# 03_SigPart.net
KiCad netlist of a schematic drawn in EasyEDA Pro
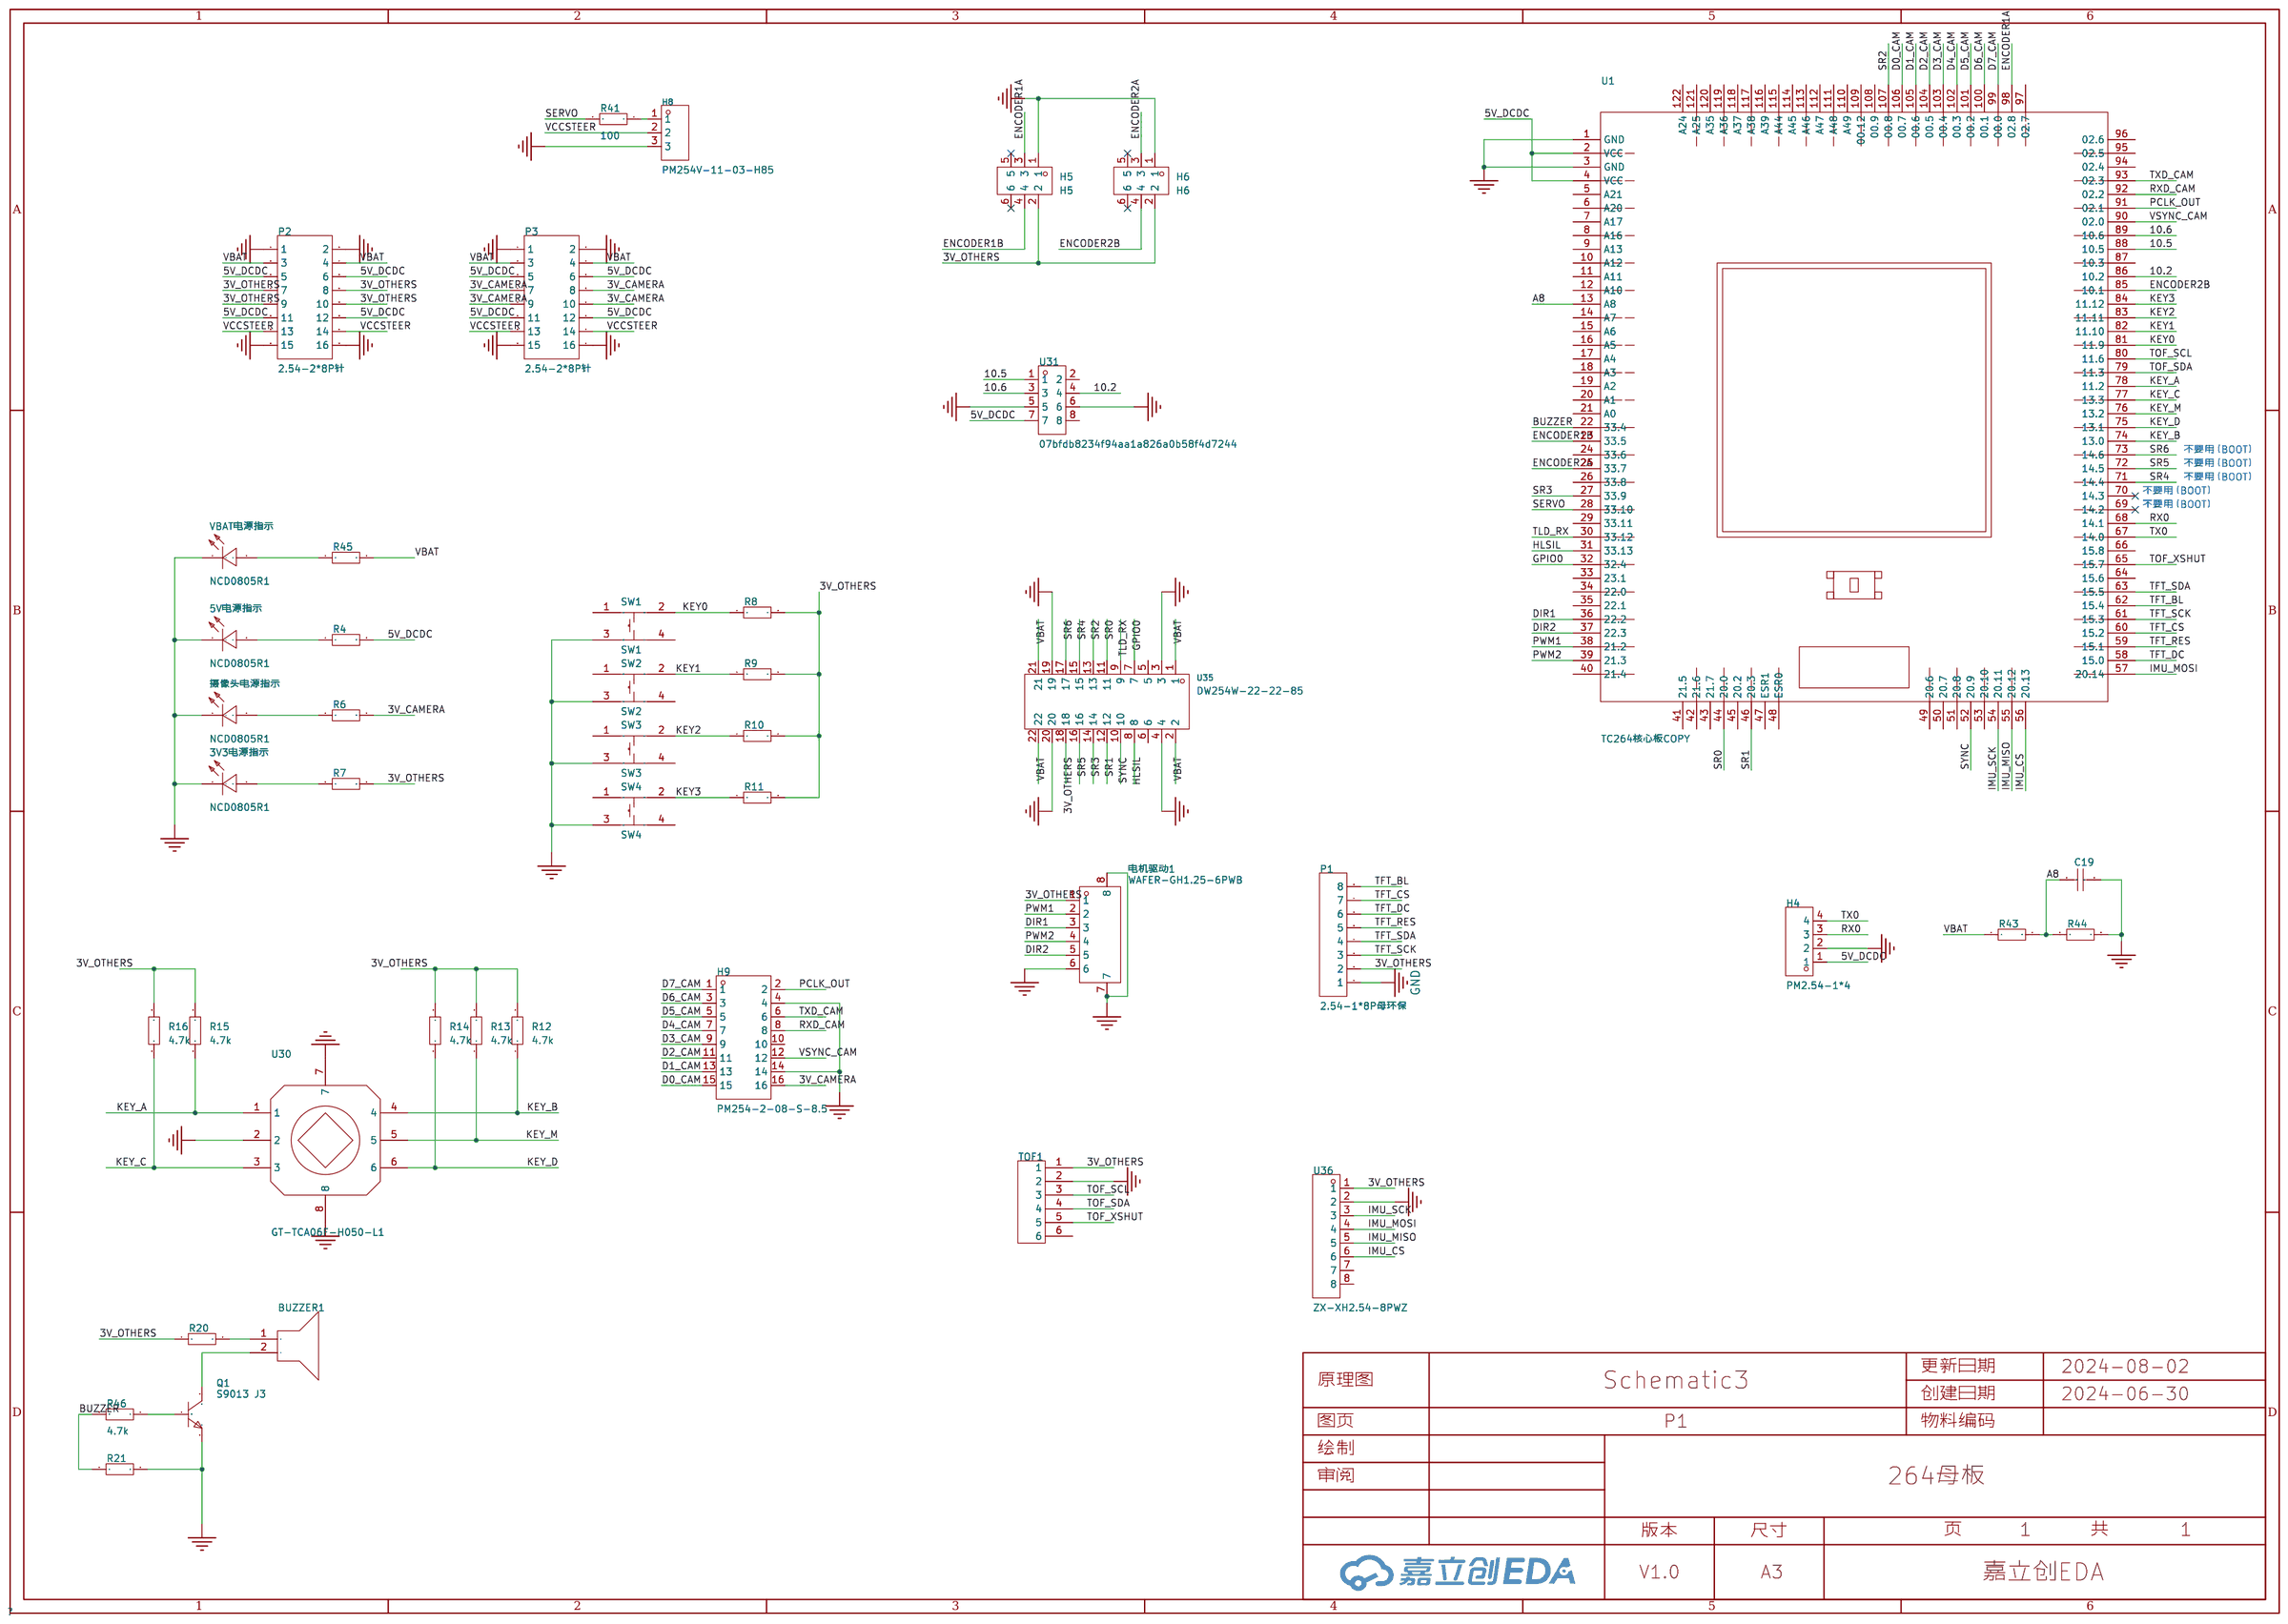
[diagram p0: schematic sheet]

(export (version "E")
  (design (tool "Eeschema 10.0.6"))
  (components
    (comp (ref "3V3电源指示")
      (value "NCD0805R1")
      (footprint "easyedapro:LED0805-RD")
      (description "发光颜色:红灯;")
      (fields (field (name "Manufacturer") "国星光电"))
      (libsource (lib "easyedapro") (part "FC-2012HRK-620D"))
    )
    (comp (ref "5V电源指示")
      (value "NCD0805R1")
      (footprint "easyedapro:LED0805-RD")
      (description "发光颜色:红灯;")
      (fields (field (name "Manufacturer") "国星光电"))
      (libsource (lib "easyedapro") (part "FC-2012HRK-620D"))
    )
    (comp (ref "BUZZER1")
      (value "SFN-1270-0540-35P5.0")
      (footprint "easyedapro:BUZ-TH_BD12.5-P5.00-D0.9")
      (description "驱动方式：无源(外部驱动) 构造类型：压电式 额定电压：5V 频率：4000Hz 声压(SPL)：80dB@5V,10cm 直径(φD)：12.6mm 高度：7.5mm")
      (fields (field (name "Manufacturer") "SS(海旭)"))
      (libsource (lib "easyedapro") (part "BUZZER"))
    )
    (comp (ref "C19")
      (value "100nF")
      (footprint "easyedapro:C0805")
      (libsource (lib "easyedapro") (part "电容-0805C"))
    )
    (comp (ref "H4")
      (value "PM2.54-1*4")
      (footprint "easyedapro:HDR-TH_4P-P2.54-V-F")
      (fields (field (name "Manufacturer") "ZHOURI(洲日)"))
      (libsource (lib "easyedapro") (part "PM2.54-1*4"))
    )
    (comp (ref "H5")
      (value "H5")
      (footprint "easyedapro:HDR-SMD_6P-P2.54-V-M-R2-C5-S7.4")
      (fields
        (field (name "Manufacturer Part") "X6521WVS-2x03H-C60D74")
        (field (name "Manufacturer") "XKB Connectivity(中国星坤)")
      )
      (libsource (lib "easyedapro") (part "X6521WVS-2x03H-C60D74"))
    )
    (comp (ref "H6")
      (value "H6")
      (footprint "easyedapro:HDR-SMD_6P-P2.54-V-M-R2-C5-S7.4")
      (fields
        (field (name "Manufacturer Part") "X6521WVS-2x03H-C60D74")
        (field (name "Manufacturer") "XKB Connectivity(中国星坤)")
      )
      (libsource (lib "easyedapro") (part "X6521WVS-2x03H-C60D74"))
    )
    (comp (ref "H8")
      (value "PM254V-11-03-H85")
      (footprint "easyedapro:HDR-TH_3P-P2.54-V-F")
      (description "排数:单排;总孔位数:3P;间距:2.54mm;插孔结构:1x3P;")
      (fields (field (name "Manufacturer") "XFCN(兴飞)"))
      (libsource (lib "easyedapro") (part "PM254_1*3"))
    )
    (comp (ref "H9")
      (value "PM254-2-08-S-8.5")
      (footprint "easyedapro:HDR-SMD_16P-P2.54-V-F-R2-C8-LS7.1")
      (fields (field (name "Manufacturer") "HCTL(华灿天禄)"))
      (libsource (lib "easyedapro") (part "PM254-2-08-S-8.5"))
    )
    (comp (ref "P1")
      (value "2.54-1*8P母环保")
      (footprint "easyedapro:HDR-TH_8P-P2.54-V-F-1")
      (description "排数:单排;总孔位数:8;间距:2.54mm;插孔结构:1x8P;行距:-;安装类型:直插;塑高:-;触头材质:-;触头镀层:-;")
      (fields (field (name "Manufacturer") "BOOMELE(博穆精密)"))
      (libsource (lib "easyedapro") (part "Header-Female-2.54_1x8"))
    )
    (comp (ref "P2")
      (value "2.54-2*8P针")
      (footprint "easyedapro:HDR-TH_16P-P2.54-V-M-R2-C8-S2.54")
      (fields (field (name "Manufacturer") "BOOMELE(博穆精密)"))
      (libsource (lib "easyedapro") (part "Header-Male-2.54_2x8"))
    )
    (comp (ref "P3")
      (value "2.54-2*8P针")
      (footprint "easyedapro:HDR-TH_16P-P2.54-V-M-R2-C8-S2.54")
      (fields (field (name "Manufacturer") "BOOMELE(博穆精密)"))
      (libsource (lib "easyedapro") (part "Header-Male-2.54_2x8"))
    )
    (comp (ref "Q1")
      (value "S9013 J3")
      (footprint "easyedapro:SOT-23-3_L2.9-W1.3-P1.90-LS2.4-BR")
      (description "晶体管类型:NPN;集电极电流(Ic):500mA;集射极击穿电压(Vceo):25V;功率(Pd):300mW;直流电流增益(hFE@Ic,Vce):200@50mA,1V;")
      (fields (field (name "Manufacturer") "CJ(江苏长电/长晶)"))
      (libsource (lib "easyedapro") (part "S9013 J3"))
    )
    (comp (ref "R4")
      (value "4.7k")
      (footprint "easyedapro:R0805")
      (description "电阻类型:厚膜电阻;阻值:1kΩ;精度:±1%;功率:125mW;温度系数:±100ppm/°C;最大工作电压:150V;工作温度范围:-55°C~+155°C;")
      (libsource (lib "easyedapro") (part "电阻_0805"))
    )
    (comp (ref "R6")
      (value "4.7k")
      (footprint "easyedapro:R0805")
      (description "电阻类型:厚膜电阻;阻值:1kΩ;精度:±1%;功率:125mW;温度系数:±100ppm/°C;最大工作电压:150V;工作温度范围:-55°C~+155°C;")
      (libsource (lib "easyedapro") (part "电阻_0805"))
    )
    (comp (ref "R7")
      (value "4.7k")
      (footprint "easyedapro:R0805")
      (description "电阻类型:厚膜电阻;阻值:1kΩ;精度:±1%;功率:125mW;温度系数:±100ppm/°C;最大工作电压:150V;工作温度范围:-55°C~+155°C;")
      (libsource (lib "easyedapro") (part "电阻_0805"))
    )
    (comp (ref "R8")
      (value "4.7k")
      (footprint "easyedapro:R0805")
      (description "电阻类型:厚膜电阻;阻值:1kΩ;精度:±1%;功率:125mW;温度系数:±100ppm/°C;最大工作电压:150V;工作温度范围:-55°C~+155°C;")
      (libsource (lib "easyedapro") (part "电阻_0805"))
    )
    (comp (ref "R9")
      (value "4.7k")
      (footprint "easyedapro:R0805")
      (description "电阻类型:厚膜电阻;阻值:1kΩ;精度:±1%;功率:125mW;温度系数:±100ppm/°C;最大工作电压:150V;工作温度范围:-55°C~+155°C;")
      (libsource (lib "easyedapro") (part "电阻_0805"))
    )
    (comp (ref "R10")
      (value "4.7k")
      (footprint "easyedapro:R0805")
      (description "电阻类型:厚膜电阻;阻值:1kΩ;精度:±1%;功率:125mW;温度系数:±100ppm/°C;最大工作电压:150V;工作温度范围:-55°C~+155°C;")
      (libsource (lib "easyedapro") (part "电阻_0805"))
    )
    (comp (ref "R11")
      (value "4.7k")
      (footprint "easyedapro:R0805")
      (description "电阻类型:厚膜电阻;阻值:1kΩ;精度:±1%;功率:125mW;温度系数:±100ppm/°C;最大工作电压:150V;工作温度范围:-55°C~+155°C;")
      (libsource (lib "easyedapro") (part "电阻_0805"))
    )
    (comp (ref "R12")
      (value "4.7k")
      (footprint "easyedapro:R0805")
      (description "电阻类型:厚膜电阻;阻值:1kΩ;精度:±1%;功率:125mW;温度系数:±100ppm/°C;最大工作电压:150V;工作温度范围:-55°C~+155°C;")
      (libsource (lib "easyedapro") (part "电阻_0805"))
    )
    (comp (ref "R13")
      (value "4.7k")
      (footprint "easyedapro:R0805")
      (description "电阻类型:厚膜电阻;阻值:1kΩ;精度:±1%;功率:125mW;温度系数:±100ppm/°C;最大工作电压:150V;工作温度范围:-55°C~+155°C;")
      (libsource (lib "easyedapro") (part "电阻_0805"))
    )
    (comp (ref "R14")
      (value "4.7k")
      (footprint "easyedapro:R0805")
      (description "电阻类型:厚膜电阻;阻值:1kΩ;精度:±1%;功率:125mW;温度系数:±100ppm/°C;最大工作电压:150V;工作温度范围:-55°C~+155°C;")
      (libsource (lib "easyedapro") (part "电阻_0805"))
    )
    (comp (ref "R15")
      (value "4.7k")
      (footprint "easyedapro:R0805")
      (description "电阻类型:厚膜电阻;阻值:1kΩ;精度:±1%;功率:125mW;温度系数:±100ppm/°C;最大工作电压:150V;工作温度范围:-55°C~+155°C;")
      (libsource (lib "easyedapro") (part "电阻_0805"))
    )
    (comp (ref "R16")
      (value "4.7k")
      (footprint "easyedapro:R0805")
      (description "电阻类型:厚膜电阻;阻值:1kΩ;精度:±1%;功率:125mW;温度系数:±100ppm/°C;最大工作电压:150V;工作温度范围:-55°C~+155°C;")
      (libsource (lib "easyedapro") (part "电阻_0805"))
    )
    (comp (ref "R20")
      (value "10R")
      (footprint "easyedapro:R0805")
      (description "电阻类型:厚膜电阻;阻值:1kΩ;精度:±1%;功率:125mW;温度系数:±100ppm/°C;最大工作电压:150V;工作温度范围:-55°C~+155°C;")
      (libsource (lib "easyedapro") (part "电阻_0805"))
    )
    (comp (ref "R21")
      (value "10k")
      (footprint "easyedapro:R0805")
      (description "电阻类型:厚膜电阻;阻值:1kΩ;精度:±1%;功率:125mW;温度系数:±100ppm/°C;最大工作电压:150V;工作温度范围:-55°C~+155°C;")
      (libsource (lib "easyedapro") (part "电阻_0805"))
    )
    (comp (ref "R41")
      (value "100")
      (footprint "easyedapro:R0805")
      (description "电阻类型:厚膜电阻;阻值:1kΩ;精度:±1%;功率:125mW;温度系数:±100ppm/°C;最大工作电压:150V;工作温度范围:-55°C~+155°C;")
      (libsource (lib "easyedapro") (part "电阻_0805"))
    )
    (comp (ref "R43")
      (value "30k")
      (footprint "easyedapro:R0805")
      (description "电阻类型:厚膜电阻;阻值:1kΩ;精度:±1%;功率:125mW;温度系数:±100ppm/°C;最大工作电压:150V;工作温度范围:-55°C~+155°C;")
      (libsource (lib "easyedapro") (part "电阻_0805"))
    )
    (comp (ref "R44")
      (value "10k")
      (footprint "easyedapro:R0805")
      (description "电阻类型:厚膜电阻;阻值:1kΩ;精度:±1%;功率:125mW;温度系数:±100ppm/°C;最大工作电压:150V;工作温度范围:-55°C~+155°C;")
      (libsource (lib "easyedapro") (part "电阻_0805"))
    )
    (comp (ref "R45")
      (value "4.7k")
      (footprint "easyedapro:R0805")
      (description "电阻类型:厚膜电阻;阻值:1kΩ;精度:±1%;功率:125mW;温度系数:±100ppm/°C;最大工作电压:150V;工作温度范围:-55°C~+155°C;")
      (libsource (lib "easyedapro") (part "电阻_0805"))
    )
    (comp (ref "R46")
      (value "4.7k")
      (footprint "easyedapro:R0805")
      (description "电阻类型:厚膜电阻;阻值:1kΩ;精度:±1%;功率:125mW;温度系数:±100ppm/°C;最大工作电压:150V;工作温度范围:-55°C~+155°C;")
      (libsource (lib "easyedapro") (part "电阻_0805"))
    )
    (comp (ref "SW1")
      (value "SW1")
      (fields (field (name "Manufacturer Part") "K2-1808SN-A3SW-01") (field (name "Manufacturer") "韩国韩荣"))
      (libsource (lib "easyedapro") (part "K2-1808SN-A3SW-01"))
    )
    (comp (ref "SW2")
      (value "SW2")
      (fields (field (name "Manufacturer Part") "K2-1808SN-A3SW-01") (field (name "Manufacturer") "韩国韩荣"))
      (libsource (lib "easyedapro") (part "K2-1808SN-A3SW-01"))
    )
    (comp (ref "SW3")
      (value "SW3")
      (fields (field (name "Manufacturer Part") "K2-1808SN-A3SW-01") (field (name "Manufacturer") "韩国韩荣"))
      (libsource (lib "easyedapro") (part "K2-1808SN-A3SW-01"))
    )
    (comp (ref "SW4")
      (value "SW4")
      (fields (field (name "Manufacturer Part") "K2-1808SN-A3SW-01") (field (name "Manufacturer") "韩国韩荣"))
      (libsource (lib "easyedapro") (part "K2-1808SN-A3SW-01"))
    )
    (comp (ref "TOF1")
      (value "~")
      (footprint "easyedapro:CONN-TH_6P-P2.50_XH-6A")
      (libsource (lib "easyedapro") (part "XH-6直插"))
    )
    (comp (ref "U1")
      (value "TC264核心板COPY")
      (footprint "easyedapro:TC264逐飞")
      (libsource (lib "easyedapro") (part "TC264核心板 COPY"))
    )
    (comp (ref "U30")
      (value "GT-TCA06F-H050-L1")
      (footprint "easyedapro:KEY-SMD_GT-TCA06F-H050-L1")
      (description "开关长度:7.5mm;开关宽度:7.5mm;开关高度:5mm;机械寿命:-;")
      (fields (field (name "Manufacturer") "G-Switch(品赞)"))
      (libsource (lib "easyedapro") (part "GT-TCA06F-H050-L1"))
    )
    (comp (ref "U31")
      (value "07bfdb8234f94aa1a826a0b58f4d7244")
      (footprint "easyedapro:HDR-TH_8P-P2.54-V-F-R2-C4-S2.54")
      (fields (field (name "Manufacturer Part") "2.54-2*4") (field (name "Manufacturer") "ZHOURI(洲日)"))
      (libsource (lib "easyedapro") (part "PM2.54-2*4"))
    )
    (comp (ref "U35")
      (value "DW254W-22-22-85")
      (footprint "easyedapro:CONN-TH_22P-P2.54_DEALON_DW254W-22-22-85")
      (description "插孔结构:2x11P;间距:2.54mm;安装类型:弯插;排数:双排;")
      (fields (field (name "Manufacturer") "DEALON(德艺隆)"))
      (libsource (lib "easyedapro") (part "DW254W-22-22-85"))
    )
    (comp (ref "U36")
      (value "ZX-XH2.54-8PWZ")
      (footprint "easyedapro:CONN-TH_8P-P2.50_ZX-XH2.54-8PWZ")
      (fields (field (name "Manufacturer") "Megastar(兆星)"))
      (libsource (lib "easyedapro") (part "ZX-XH2.54-8PWZ"))
    )
    (comp (ref "VBAT电源指示")
      (value "NCD0805R1")
      (footprint "easyedapro:LED0805-RD")
      (description "发光颜色:红灯;")
      (fields (field (name "Manufacturer") "国星光电"))
      (libsource (lib "easyedapro") (part "FC-2012HRK-620D"))
    )
    (comp (ref "摄像头电源指示")
      (value "NCD0805R1")
      (footprint "easyedapro:LED0805-RD")
      (description "发光颜色:红灯;")
      (fields (field (name "Manufacturer") "国星光电"))
      (libsource (lib "easyedapro") (part "FC-2012HRK-620D"))
    )
    (comp (ref "电机驱动1")
      (value "WAFER-GH1.25-6PWB")
      (footprint "easyedapro:CONN-SMD_6P-P1.25_XUNPU_WAFER-GH1.25-6PWB")
      (description "插针结构:1x6P;间距:1.25mm;安装方式:卧贴;参考系列:GH;总PIN数:6P;排数:1;每排PIN数:6;额定电流:1A;工作温度范围:-25°C~+85°C;")
      (fields (field (name "Manufacturer") "XUNPU(讯普)"))
      (libsource (lib "easyedapro") (part "WAFER-GH1.25-6PWB"))
    )
  )
  (nets
    (net (code "1") (name "/3V_CAMERA") (class "Default")
      (node (ref "H9") (pin "16") (pinfunction "16_16") (pintype "unspecified"))
      (node (ref "P3") (pin "10") (pinfunction "10_10") (pintype "input"))
      (node (ref "P3") (pin "7") (pinfunction "7_7") (pintype "input"))
      (node (ref "P3") (pin "8") (pinfunction "8_8") (pintype "input"))
      (node (ref "P3") (pin "9") (pinfunction "9_9") (pintype "input"))
      (node (ref "R6") (pin "2") (pinfunction "2_2") (pintype "input"))
    )
    (net (code "2") (name "/3V_OTHERS") (class "Default")
      (node (ref "H5") (pin "2") (pinfunction "2_2") (pintype "unspecified"))
      (node (ref "H6") (pin "2") (pinfunction "2_2") (pintype "unspecified"))
      (node (ref "P1") (pin "2") (pinfunction "2_2") (pintype "input"))
      (node (ref "P2") (pin "10") (pinfunction "10_10") (pintype "input"))
      (node (ref "P2") (pin "7") (pinfunction "7_7") (pintype "input"))
      (node (ref "P2") (pin "8") (pinfunction "8_8") (pintype "input"))
      (node (ref "P2") (pin "9") (pinfunction "9_9") (pintype "input"))
      (node (ref "R10") (pin "2") (pinfunction "2_2") (pintype "input"))
      (node (ref "R11") (pin "2") (pinfunction "2_2") (pintype "input"))
      (node (ref "R12") (pin "2") (pinfunction "2_2") (pintype "input"))
      (node (ref "R13") (pin "2") (pinfunction "2_2") (pintype "input"))
      (node (ref "R14") (pin "2") (pinfunction "2_2") (pintype "input"))
      (node (ref "R15") (pin "2") (pinfunction "2_2") (pintype "input"))
      (node (ref "R16") (pin "2") (pinfunction "2_2") (pintype "input"))
      (node (ref "R20") (pin "1") (pinfunction "1_1") (pintype "input"))
      (node (ref "R7") (pin "2") (pinfunction "2_2") (pintype "input"))
      (node (ref "R8") (pin "2") (pinfunction "2_2") (pintype "input"))
      (node (ref "R9") (pin "2") (pinfunction "2_2") (pintype "input"))
      (node (ref "TOF1") (pin "1") (pinfunction "1_1") (pintype "input"))
      (node (ref "U35") (pin "18") (pinfunction "18_18") (pintype "input"))
      (node (ref "U36") (pin "1") (pinfunction "1_1") (pintype "unspecified"))
      (node (ref "电机驱动1") (pin "1") (pinfunction "1_1") (pintype "unspecified"))
    )
    (net (code "3") (name "/5V_DCDC") (class "Default")
      (node (ref "H4") (pin "1") (pinfunction "1_1") (pintype "input"))
      (node (ref "P2") (pin "11") (pinfunction "11_11") (pintype "input"))
      (node (ref "P2") (pin "12") (pinfunction "12_12") (pintype "input"))
      (node (ref "P2") (pin "5") (pinfunction "5_5") (pintype "input"))
      (node (ref "P2") (pin "6") (pinfunction "6_6") (pintype "input"))
      (node (ref "P3") (pin "11") (pinfunction "11_11") (pintype "input"))
      (node (ref "P3") (pin "12") (pinfunction "12_12") (pintype "input"))
      (node (ref "P3") (pin "5") (pinfunction "5_5") (pintype "input"))
      (node (ref "P3") (pin "6") (pinfunction "6_6") (pintype "input"))
      (node (ref "R4") (pin "2") (pinfunction "2_2") (pintype "input"))
      (node (ref "U1") (pin "2") (pinfunction "VCC_2") (pintype "input"))
      (node (ref "U1") (pin "4") (pinfunction "VCC_4") (pintype "input"))
      (node (ref "U31") (pin "7") (pinfunction "7_7") (pintype "input"))
    )
    (net (code "4") (name "/10.2") (class "Default")
      (node (ref "U1") (pin "86") (pinfunction "10.2_86") (pintype "input"))
      (node (ref "U31") (pin "4") (pinfunction "4_4") (pintype "input"))
    )
    (net (code "5") (name "/10.5") (class "Default")
      (node (ref "U1") (pin "88") (pinfunction "10.5_88") (pintype "input"))
      (node (ref "U31") (pin "1") (pinfunction "1_1") (pintype "input"))
    )
    (net (code "6") (name "/10.6") (class "Default")
      (node (ref "U1") (pin "89") (pinfunction "10.6_89") (pintype "input"))
      (node (ref "U31") (pin "3") (pinfunction "3_3") (pintype "input"))
    )
    (net (code "7") (name "/A8") (class "Default")
      (node (ref "C19") (pin "1") (pinfunction "1_1") (pintype "input"))
      (node (ref "R43") (pin "2") (pinfunction "2_2") (pintype "input"))
      (node (ref "R44") (pin "1") (pinfunction "1_1") (pintype "input"))
      (node (ref "U1") (pin "13") (pinfunction "A8_13") (pintype "input"))
    )
    (net (code "8") (name "/BUZZER") (class "Default")
      (node (ref "R21") (pin "1") (pinfunction "1_1") (pintype "input"))
      (node (ref "R46") (pin "2") (pinfunction "2_2") (pintype "input"))
      (node (ref "U1") (pin "22") (pinfunction "33.4_22") (pintype "input"))
    )
    (net (code "9") (name "/D0_CAM") (class "Default")
      (node (ref "H9") (pin "15") (pinfunction "15_15") (pintype "unspecified"))
      (node (ref "U1") (pin "106") (pinfunction "00.7_106") (pintype "input"))
    )
    (net (code "10") (name "/D1_CAM") (class "Default")
      (node (ref "H9") (pin "13") (pinfunction "13_13") (pintype "unspecified"))
      (node (ref "U1") (pin "105") (pinfunction "00.6_105") (pintype "input"))
    )
    (net (code "11") (name "/D2_CAM") (class "Default")
      (node (ref "H9") (pin "11") (pinfunction "11_11") (pintype "unspecified"))
      (node (ref "U1") (pin "104") (pinfunction "00.5_104") (pintype "input"))
    )
    (net (code "12") (name "/D3_CAM") (class "Default")
      (node (ref "H9") (pin "9") (pinfunction "9_9") (pintype "unspecified"))
      (node (ref "U1") (pin "103") (pinfunction "00.4_103") (pintype "input"))
    )
    (net (code "13") (name "/D4_CAM") (class "Default")
      (node (ref "H9") (pin "7") (pinfunction "7_7") (pintype "unspecified"))
      (node (ref "U1") (pin "102") (pinfunction "00.3_102") (pintype "input"))
    )
    (net (code "14") (name "/D5_CAM") (class "Default")
      (node (ref "H9") (pin "5") (pinfunction "5_5") (pintype "unspecified"))
      (node (ref "U1") (pin "101") (pinfunction "00.2_101") (pintype "input"))
    )
    (net (code "15") (name "/D6_CAM") (class "Default")
      (node (ref "H9") (pin "3") (pinfunction "3_3") (pintype "unspecified"))
      (node (ref "U1") (pin "100") (pinfunction "00.1_100") (pintype "input"))
    )
    (net (code "16") (name "/D7_CAM") (class "Default")
      (node (ref "H9") (pin "1") (pinfunction "1_1") (pintype "unspecified"))
      (node (ref "U1") (pin "99") (pinfunction "00.0_99") (pintype "input"))
    )
    (net (code "17") (name "/DIR1") (class "Default")
      (node (ref "U1") (pin "36") (pinfunction "22.2_36") (pintype "input"))
      (node (ref "电机驱动1") (pin "3") (pinfunction "3_3") (pintype "unspecified"))
    )
    (net (code "18") (name "/DIR2") (class "Default")
      (node (ref "U1") (pin "37") (pinfunction "22.3_37") (pintype "input"))
      (node (ref "电机驱动1") (pin "5") (pinfunction "5_5") (pintype "unspecified"))
    )
    (net (code "19") (name "/ENCODER1A") (class "Default")
      (node (ref "H5") (pin "3") (pinfunction "3_3") (pintype "unspecified"))
      (node (ref "U1") (pin "98") (pinfunction "02.8_98") (pintype "input"))
    )
    (net (code "20") (name "/ENCODER1B") (class "Default")
      (node (ref "H5") (pin "4") (pinfunction "4_4") (pintype "unspecified"))
      (node (ref "U1") (pin "23") (pinfunction "33.5_23") (pintype "input"))
    )
    (net (code "21") (name "/ENCODER2A") (class "Default")
      (node (ref "H6") (pin "3") (pinfunction "3_3") (pintype "unspecified"))
      (node (ref "U1") (pin "25") (pinfunction "33.7_25") (pintype "input"))
    )
    (net (code "22") (name "/ENCODER2B") (class "Default")
      (node (ref "H6") (pin "4") (pinfunction "4_4") (pintype "unspecified"))
      (node (ref "U1") (pin "85") (pinfunction "10.1_85") (pintype "input"))
    )
    (net (code "23") (name "/GPIO0") (class "Default")
      (node (ref "U1") (pin "32") (pinfunction "32.4_32") (pintype "input"))
      (node (ref "U35") (pin "7") (pinfunction "7_7") (pintype "input"))
    )
    (net (code "24") (name "/HLSIL") (class "Default")
      (node (ref "U1") (pin "31") (pinfunction "33.13_31") (pintype "input"))
      (node (ref "U35") (pin "8") (pinfunction "8_8") (pintype "input"))
    )
    (net (code "25") (name "/IMU_CS") (class "Default")
      (node (ref "U1") (pin "56") (pinfunction "20.13_56") (pintype "input"))
      (node (ref "U36") (pin "6") (pinfunction "6_6") (pintype "unspecified"))
    )
    (net (code "26") (name "/IMU_MISO") (class "Default")
      (node (ref "U1") (pin "55") (pinfunction "20.12_55") (pintype "input"))
      (node (ref "U36") (pin "5") (pinfunction "5_5") (pintype "unspecified"))
    )
    (net (code "27") (name "/IMU_MOSI") (class "Default")
      (node (ref "U1") (pin "57") (pinfunction "20.14_57") (pintype "input"))
      (node (ref "U36") (pin "4") (pinfunction "4_4") (pintype "unspecified"))
    )
    (net (code "28") (name "/IMU_SCK") (class "Default")
      (node (ref "U1") (pin "54") (pinfunction "20.11_54") (pintype "input"))
      (node (ref "U36") (pin "3") (pinfunction "3_3") (pintype "unspecified"))
    )
    (net (code "29") (name "/KEY0") (class "Default")
      (node (ref "R8") (pin "1") (pinfunction "1_1") (pintype "input"))
      (node (ref "SW1") (pin "2") (pinfunction "2_2") (pintype "input"))
      (node (ref "U1") (pin "81") (pinfunction "11.9_81") (pintype "input"))
    )
    (net (code "30") (name "/KEY1") (class "Default")
      (node (ref "R9") (pin "1") (pinfunction "1_1") (pintype "input"))
      (node (ref "SW2") (pin "2") (pinfunction "2_2") (pintype "input"))
      (node (ref "U1") (pin "82") (pinfunction "11.10_82") (pintype "input"))
    )
    (net (code "31") (name "/KEY2") (class "Default")
      (node (ref "R10") (pin "1") (pinfunction "1_1") (pintype "input"))
      (node (ref "SW3") (pin "2") (pinfunction "2_2") (pintype "input"))
      (node (ref "U1") (pin "83") (pinfunction "11.11_83") (pintype "input"))
    )
    (net (code "32") (name "/KEY3") (class "Default")
      (node (ref "R11") (pin "1") (pinfunction "1_1") (pintype "input"))
      (node (ref "SW4") (pin "2") (pinfunction "2_2") (pintype "input"))
      (node (ref "U1") (pin "84") (pinfunction "11.12_84") (pintype "input"))
    )
    (net (code "33") (name "/KEY_A") (class "Default")
      (node (ref "R15") (pin "1") (pinfunction "1_1") (pintype "input"))
      (node (ref "U1") (pin "78") (pinfunction "11.2_78") (pintype "input"))
      (node (ref "U30") (pin "1") (pinfunction "1_1") (pintype "unspecified"))
    )
    (net (code "34") (name "/KEY_B") (class "Default")
      (node (ref "R12") (pin "1") (pinfunction "1_1") (pintype "input"))
      (node (ref "U1") (pin "74") (pinfunction "13.0_74") (pintype "input"))
      (node (ref "U30") (pin "4") (pinfunction "4_4") (pintype "unspecified"))
    )
    (net (code "35") (name "/KEY_C") (class "Default")
      (node (ref "R16") (pin "1") (pinfunction "1_1") (pintype "input"))
      (node (ref "U1") (pin "77") (pinfunction "13.3_77") (pintype "input"))
      (node (ref "U30") (pin "3") (pinfunction "3_3") (pintype "unspecified"))
    )
    (net (code "36") (name "/KEY_D") (class "Default")
      (node (ref "R14") (pin "1") (pinfunction "1_1") (pintype "input"))
      (node (ref "U1") (pin "75") (pinfunction "13.1_75") (pintype "input"))
      (node (ref "U30") (pin "6") (pinfunction "6_6") (pintype "unspecified"))
    )
    (net (code "37") (name "/KEY_M") (class "Default")
      (node (ref "R13") (pin "1") (pinfunction "1_1") (pintype "input"))
      (node (ref "U1") (pin "76") (pinfunction "13.2_76") (pintype "input"))
      (node (ref "U30") (pin "5") (pinfunction "5_5") (pintype "unspecified"))
    )
    (net (code "38") (name "/PCLK_OUT") (class "Default")
      (node (ref "H9") (pin "2") (pinfunction "2_2") (pintype "unspecified"))
      (node (ref "U1") (pin "91") (pinfunction "02.1_91") (pintype "input"))
    )
    (net (code "39") (name "/PWM1") (class "Default")
      (node (ref "U1") (pin "38") (pinfunction "21.2_38") (pintype "input"))
      (node (ref "电机驱动1") (pin "2") (pinfunction "2_2") (pintype "unspecified"))
    )
    (net (code "40") (name "/PWM2") (class "Default")
      (node (ref "U1") (pin "39") (pinfunction "21.3_39") (pintype "input"))
      (node (ref "电机驱动1") (pin "4") (pinfunction "4_4") (pintype "unspecified"))
    )
    (net (code "41") (name "/RX0") (class "Default")
      (node (ref "H4") (pin "3") (pinfunction "3_3") (pintype "input"))
      (node (ref "U1") (pin "68") (pinfunction "14.1_68") (pintype "input"))
    )
    (net (code "42") (name "/RXD_CAM") (class "Default")
      (node (ref "H9") (pin "8") (pinfunction "8_8") (pintype "unspecified"))
      (node (ref "U1") (pin "92") (pinfunction "02.2_92") (pintype "input"))
    )
    (net (code "43") (name "/SERVO") (class "Default")
      (node (ref "R41") (pin "2") (pinfunction "2_2") (pintype "input"))
      (node (ref "U1") (pin "28") (pinfunction "33.10_28") (pintype "input"))
    )
    (net (code "44") (name "/SR0") (class "Default")
      (node (ref "U1") (pin "44") (pinfunction "20.0_44") (pintype "input"))
      (node (ref "U35") (pin "11") (pinfunction "11_11") (pintype "input"))
    )
    (net (code "45") (name "/SR1") (class "Default")
      (node (ref "U1") (pin "46") (pinfunction "20.3_46") (pintype "input"))
      (node (ref "U35") (pin "12") (pinfunction "12_12") (pintype "input"))
    )
    (net (code "46") (name "/SR2") (class "Default")
      (node (ref "U1") (pin "107") (pinfunction "00.8_107") (pintype "input"))
      (node (ref "U35") (pin "13") (pinfunction "13_13") (pintype "input"))
    )
    (net (code "47") (name "/SR3") (class "Default")
      (node (ref "U1") (pin "27") (pinfunction "33.9_27") (pintype "input"))
      (node (ref "U35") (pin "14") (pinfunction "14_14") (pintype "input"))
    )
    (net (code "48") (name "/SR4") (class "Default")
      (node (ref "U1") (pin "71") (pinfunction "14.4_71") (pintype "input"))
      (node (ref "U35") (pin "15") (pinfunction "15_15") (pintype "input"))
    )
    (net (code "49") (name "/SR5") (class "Default")
      (node (ref "U1") (pin "72") (pinfunction "14.5_72") (pintype "input"))
      (node (ref "U35") (pin "16") (pinfunction "16_16") (pintype "input"))
    )
    (net (code "50") (name "/SR6") (class "Default")
      (node (ref "U1") (pin "73") (pinfunction "14.6_73") (pintype "input"))
      (node (ref "U35") (pin "17") (pinfunction "17_17") (pintype "input"))
    )
    (net (code "51") (name "/SYNC") (class "Default")
      (node (ref "U1") (pin "52") (pinfunction "20.9_52") (pintype "input"))
      (node (ref "U35") (pin "10") (pinfunction "10_10") (pintype "input"))
    )
    (net (code "52") (name "/TFT_BL") (class "Default")
      (node (ref "P1") (pin "8") (pinfunction "8_8") (pintype "input"))
      (node (ref "U1") (pin "62") (pinfunction "15.4_62") (pintype "input"))
    )
    (net (code "53") (name "/TFT_CS") (class "Default")
      (node (ref "P1") (pin "7") (pinfunction "7_7") (pintype "input"))
      (node (ref "U1") (pin "60") (pinfunction "15.2_60") (pintype "input"))
    )
    (net (code "54") (name "/TFT_DC") (class "Default")
      (node (ref "P1") (pin "6") (pinfunction "6_6") (pintype "input"))
      (node (ref "U1") (pin "58") (pinfunction "15.0_58") (pintype "input"))
    )
    (net (code "55") (name "/TFT_RES") (class "Default")
      (node (ref "P1") (pin "5") (pinfunction "5_5") (pintype "input"))
      (node (ref "U1") (pin "59") (pinfunction "15.1_59") (pintype "input"))
    )
    (net (code "56") (name "/TFT_SCK") (class "Default")
      (node (ref "P1") (pin "3") (pinfunction "3_3") (pintype "input"))
      (node (ref "U1") (pin "61") (pinfunction "15.3_61") (pintype "input"))
    )
    (net (code "57") (name "/TFT_SDA") (class "Default")
      (node (ref "P1") (pin "4") (pinfunction "4_4") (pintype "input"))
      (node (ref "U1") (pin "63") (pinfunction "15.5_63") (pintype "input"))
    )
    (net (code "58") (name "/TLD_RX") (class "Default")
      (node (ref "U1") (pin "30") (pinfunction "33.12_30") (pintype "input"))
      (node (ref "U35") (pin "9") (pinfunction "9_9") (pintype "input"))
    )
    (net (code "59") (name "/TOF_SCL") (class "Default")
      (node (ref "TOF1") (pin "3") (pinfunction "3_3") (pintype "input"))
      (node (ref "U1") (pin "80") (pinfunction "11.6_80") (pintype "input"))
    )
    (net (code "60") (name "/TOF_SDA") (class "Default")
      (node (ref "TOF1") (pin "4") (pinfunction "4_4") (pintype "input"))
      (node (ref "U1") (pin "79") (pinfunction "11.3_79") (pintype "input"))
    )
    (net (code "61") (name "/TOF_XSHUT") (class "Default")
      (node (ref "TOF1") (pin "5") (pinfunction "5_5") (pintype "input"))
      (node (ref "U1") (pin "65") (pinfunction "15.7_65") (pintype "input"))
    )
    (net (code "62") (name "/TX0") (class "Default")
      (node (ref "H4") (pin "4") (pinfunction "4_4") (pintype "input"))
      (node (ref "U1") (pin "67") (pinfunction "14.0_67") (pintype "input"))
    )
    (net (code "63") (name "/TXD_CAM") (class "Default")
      (node (ref "H9") (pin "6") (pinfunction "6_6") (pintype "unspecified"))
      (node (ref "U1") (pin "93") (pinfunction "02.3_93") (pintype "input"))
    )
    (net (code "64") (name "/VBAT") (class "Default")
      (node (ref "P2") (pin "3") (pinfunction "3_3") (pintype "input"))
      (node (ref "P2") (pin "4") (pinfunction "4_4") (pintype "input"))
      (node (ref "P3") (pin "3") (pinfunction "3_3") (pintype "input"))
      (node (ref "P3") (pin "4") (pinfunction "4_4") (pintype "input"))
      (node (ref "R43") (pin "1") (pinfunction "1_1") (pintype "input"))
      (node (ref "R45") (pin "2") (pinfunction "2_2") (pintype "input"))
      (node (ref "U35") (pin "1") (pinfunction "1_1") (pintype "input"))
      (node (ref "U35") (pin "2") (pinfunction "2_2") (pintype "input"))
      (node (ref "U35") (pin "21") (pinfunction "21_21") (pintype "input"))
      (node (ref "U35") (pin "22") (pinfunction "22_22") (pintype "input"))
    )
    (net (code "65") (name "/VCCSTEER") (class "Default")
      (node (ref "H8") (pin "2") (pinfunction "2_2") (pintype "input"))
      (node (ref "P2") (pin "13") (pinfunction "13_13") (pintype "input"))
      (node (ref "P2") (pin "14") (pinfunction "14_14") (pintype "input"))
      (node (ref "P3") (pin "13") (pinfunction "13_13") (pintype "input"))
      (node (ref "P3") (pin "14") (pinfunction "14_14") (pintype "input"))
    )
    (net (code "66") (name "/VSYNC_CAM") (class "Default")
      (node (ref "H9") (pin "12") (pinfunction "12_12") (pintype "unspecified"))
      (node (ref "U1") (pin "90") (pinfunction "02.0_90") (pintype "input"))
    )
    (net (code "67") (name "GND") (class "Default")
      (node (ref "3V3电源指示") (pin "1") (pinfunction "-_1") (pintype "input"))
      (node (ref "5V电源指示") (pin "1") (pinfunction "-_1") (pintype "input"))
      (node (ref "C19") (pin "2") (pinfunction "2_2") (pintype "input"))
      (node (ref "H4") (pin "2") (pinfunction "2_2") (pintype "input"))
      (node (ref "H5") (pin "1") (pinfunction "1_1") (pintype "unspecified"))
      (node (ref "H6") (pin "1") (pinfunction "1_1") (pintype "unspecified"))
      (node (ref "H8") (pin "3") (pinfunction "3_3") (pintype "input"))
      (node (ref "H9") (pin "14") (pinfunction "14_14") (pintype "unspecified"))
      (node (ref "H9") (pin "4") (pinfunction "4_4") (pintype "unspecified"))
      (node (ref "P1") (pin "1") (pinfunction "1_1") (pintype "input"))
      (node (ref "P2") (pin "1") (pinfunction "1_1") (pintype "input"))
      (node (ref "P2") (pin "15") (pinfunction "15_15") (pintype "input"))
      (node (ref "P2") (pin "16") (pinfunction "16_16") (pintype "input"))
      (node (ref "P2") (pin "2") (pinfunction "2_2") (pintype "input"))
      (node (ref "P3") (pin "1") (pinfunction "1_1") (pintype "input"))
      (node (ref "P3") (pin "15") (pinfunction "15_15") (pintype "input"))
      (node (ref "P3") (pin "16") (pinfunction "16_16") (pintype "input"))
      (node (ref "P3") (pin "2") (pinfunction "2_2") (pintype "input"))
      (node (ref "Q1") (pin "2") (pinfunction "E_2") (pintype "unspecified"))
      (node (ref "R21") (pin "2") (pinfunction "2_2") (pintype "input"))
      (node (ref "R44") (pin "2") (pinfunction "2_2") (pintype "input"))
      (node (ref "SW1") (pin "3") (pinfunction "3_3") (pintype "input"))
      (node (ref "SW2") (pin "3") (pinfunction "3_3") (pintype "input"))
      (node (ref "SW3") (pin "3") (pinfunction "3_3") (pintype "input"))
      (node (ref "SW4") (pin "3") (pinfunction "3_3") (pintype "input"))
      (node (ref "TOF1") (pin "2") (pinfunction "2_2") (pintype "input"))
      (node (ref "U1") (pin "1") (pinfunction "GND_1") (pintype "input"))
      (node (ref "U1") (pin "3") (pinfunction "GND_3") (pintype "input"))
      (node (ref "U30") (pin "2") (pinfunction "2_2") (pintype "unspecified"))
      (node (ref "U30") (pin "7") (pinfunction "7_7") (pintype "unspecified"))
      (node (ref "U30") (pin "8") (pinfunction "8_8") (pintype "unspecified"))
      (node (ref "U31") (pin "5") (pinfunction "5_5") (pintype "input"))
      (node (ref "U31") (pin "6") (pinfunction "6_6") (pintype "input"))
      (node (ref "U35") (pin "19") (pinfunction "19_19") (pintype "input"))
      (node (ref "U35") (pin "20") (pinfunction "20_20") (pintype "input"))
      (node (ref "U35") (pin "3") (pinfunction "3_3") (pintype "input"))
      (node (ref "U35") (pin "4") (pinfunction "4_4") (pintype "input"))
      (node (ref "U36") (pin "2") (pinfunction "2_2") (pintype "unspecified"))
      (node (ref "VBAT电源指示") (pin "1") (pinfunction "-_1") (pintype "input"))
      (node (ref "摄像头电源指示") (pin "1") (pinfunction "-_1") (pintype "input"))
      (node (ref "电机驱动1") (pin "6") (pinfunction "6_6") (pintype "unspecified"))
      (node (ref "电机驱动1") (pin "7") (pinfunction "7_7") (pintype "unspecified"))
      (node (ref "电机驱动1") (pin "8") (pinfunction "8_8") (pintype "unspecified"))
    )
    (net (code "68") (name "Net-(3V3电源指示-+)") (class "Default")
      (node (ref "3V3电源指示") (pin "2") (pinfunction "+_2") (pintype "input"))
      (node (ref "R7") (pin "1") (pinfunction "1_1") (pintype "input"))
    )
    (net (code "69") (name "Net-(5V电源指示-+)") (class "Default")
      (node (ref "5V电源指示") (pin "2") (pinfunction "+_2") (pintype "input"))
      (node (ref "R4") (pin "1") (pinfunction "1_1") (pintype "input"))
    )
    (net (code "70") (name "Net-(BUZZER1-+)") (class "Default")
      (node (ref "BUZZER1") (pin "1") (pinfunction "+_1") (pintype "input"))
      (node (ref "R20") (pin "2") (pinfunction "2_2") (pintype "input"))
    )
    (net (code "71") (name "Net-(BUZZER1--)") (class "Default")
      (node (ref "BUZZER1") (pin "2") (pinfunction "-_2") (pintype "input"))
      (node (ref "Q1") (pin "3") (pinfunction "C_3") (pintype "unspecified"))
    )
    (net (code "72") (name "Net-(H8-Pad1)") (class "Default")
      (node (ref "H8") (pin "1") (pinfunction "1_1") (pintype "input"))
      (node (ref "R41") (pin "1") (pinfunction "1_1") (pintype "input"))
    )
    (net (code "73") (name "Net-(Q1-B)") (class "Default")
      (node (ref "Q1") (pin "1") (pinfunction "B_1") (pintype "unspecified"))
      (node (ref "R46") (pin "1") (pinfunction "1_1") (pintype "input"))
    )
    (net (code "74") (name "Net-(VBAT电源指示-+)") (class "Default")
      (node (ref "R45") (pin "1") (pinfunction "1_1") (pintype "input"))
      (node (ref "VBAT电源指示") (pin "2") (pinfunction "+_2") (pintype "input"))
    )
    (net (code "75") (name "Net-(摄像头电源指示-+)") (class "Default")
      (node (ref "R6") (pin "1") (pinfunction "1_1") (pintype "input"))
      (node (ref "摄像头电源指示") (pin "2") (pinfunction "+_2") (pintype "input"))
    )
    (net (code "76") (name "unconnected-(H5-Pad5)") (class "Default")
      (node (ref "H5") (pin "5") (pinfunction "5_5") (pintype "unspecified+no_connect"))
    )
    (net (code "77") (name "unconnected-(H5-Pad6)") (class "Default")
      (node (ref "H5") (pin "6") (pinfunction "6_6") (pintype "unspecified+no_connect"))
    )
    (net (code "78") (name "unconnected-(H6-Pad5)") (class "Default")
      (node (ref "H6") (pin "5") (pinfunction "5_5") (pintype "unspecified+no_connect"))
    )
    (net (code "79") (name "unconnected-(H6-Pad6)") (class "Default")
      (node (ref "H6") (pin "6") (pinfunction "6_6") (pintype "unspecified+no_connect"))
    )
    (net (code "80") (name "unconnected-(H9-Pad10)") (class "Default")
      (node (ref "H9") (pin "10") (pinfunction "10_10") (pintype "unspecified"))
    )
    (net (code "81") (name "unconnected-(SW1-Pad1)") (class "Default")
      (node (ref "SW1") (pin "1") (pinfunction "1_1") (pintype "input"))
    )
    (net (code "82") (name "unconnected-(SW1-Pad4)") (class "Default")
      (node (ref "SW1") (pin "4") (pinfunction "4_4") (pintype "input"))
    )
    (net (code "83") (name "unconnected-(SW2-Pad1)") (class "Default")
      (node (ref "SW2") (pin "1") (pinfunction "1_1") (pintype "input"))
    )
    (net (code "84") (name "unconnected-(SW2-Pad4)") (class "Default")
      (node (ref "SW2") (pin "4") (pinfunction "4_4") (pintype "input"))
    )
    (net (code "85") (name "unconnected-(SW3-Pad1)") (class "Default")
      (node (ref "SW3") (pin "1") (pinfunction "1_1") (pintype "input"))
    )
    (net (code "86") (name "unconnected-(SW3-Pad4)") (class "Default")
      (node (ref "SW3") (pin "4") (pinfunction "4_4") (pintype "input"))
    )
    (net (code "87") (name "unconnected-(SW4-Pad1)") (class "Default")
      (node (ref "SW4") (pin "1") (pinfunction "1_1") (pintype "input"))
    )
    (net (code "88") (name "unconnected-(SW4-Pad4)") (class "Default")
      (node (ref "SW4") (pin "4") (pinfunction "4_4") (pintype "input"))
    )
    (net (code "89") (name "unconnected-(TOF1-Pad6)") (class "Default")
      (node (ref "TOF1") (pin "6") (pinfunction "6_6") (pintype "input"))
    )
    (net (code "90") (name "unconnected-(U1-00.9-Pad108)") (class "Default")
      (node (ref "U1") (pin "108") (pinfunction "00.9_108") (pintype "input"))
    )
    (net (code "91") (name "unconnected-(U1-00.12-Pad109)") (class "Default")
      (node (ref "U1") (pin "109") (pinfunction "00.12_109") (pintype "input"))
    )
    (net (code "92") (name "unconnected-(U1-02.4-Pad94)") (class "Default")
      (node (ref "U1") (pin "94") (pinfunction "02.4_94") (pintype "input"))
    )
    (net (code "93") (name "unconnected-(U1-02.5-Pad95)") (class "Default")
      (node (ref "U1") (pin "95") (pinfunction "02.5_95") (pintype "input"))
    )
    (net (code "94") (name "unconnected-(U1-02.6-Pad96)") (class "Default")
      (node (ref "U1") (pin "96") (pinfunction "02.6_96") (pintype "input"))
    )
    (net (code "95") (name "unconnected-(U1-02.7-Pad97)") (class "Default")
      (node (ref "U1") (pin "97") (pinfunction "02.7_97") (pintype "input"))
    )
    (net (code "96") (name "unconnected-(U1-10.3-Pad87)") (class "Default")
      (node (ref "U1") (pin "87") (pinfunction "10.3_87") (pintype "input"))
    )
    (net (code "97") (name "unconnected-(U1-14.2-Pad69)") (class "Default")
      (node (ref "U1") (pin "69") (pinfunction "14.2_69") (pintype "input+no_connect"))
    )
    (net (code "98") (name "unconnected-(U1-14.3-Pad70)") (class "Default")
      (node (ref "U1") (pin "70") (pinfunction "14.3_70") (pintype "input+no_connect"))
    )
    (net (code "99") (name "unconnected-(U1-15.6-Pad64)") (class "Default")
      (node (ref "U1") (pin "64") (pinfunction "15.6_64") (pintype "input"))
    )
    (net (code "100") (name "unconnected-(U1-15.8-Pad66)") (class "Default")
      (node (ref "U1") (pin "66") (pinfunction "15.8_66") (pintype "input"))
    )
    (net (code "101") (name "unconnected-(U1-20.2-Pad45)") (class "Default")
      (node (ref "U1") (pin "45") (pinfunction "20.2_45") (pintype "input"))
    )
    (net (code "102") (name "unconnected-(U1-20.6-Pad49)") (class "Default")
      (node (ref "U1") (pin "49") (pinfunction "20.6_49") (pintype "input"))
    )
    (net (code "103") (name "unconnected-(U1-20.7-Pad50)") (class "Default")
      (node (ref "U1") (pin "50") (pinfunction "20.7_50") (pintype "input"))
    )
    (net (code "104") (name "unconnected-(U1-20.8-Pad51)") (class "Default")
      (node (ref "U1") (pin "51") (pinfunction "20.8_51") (pintype "input"))
    )
    (net (code "105") (name "unconnected-(U1-20.10-Pad53)") (class "Default")
      (node (ref "U1") (pin "53") (pinfunction "20.10_53") (pintype "input"))
    )
    (net (code "106") (name "unconnected-(U1-21.4-Pad40)") (class "Default")
      (node (ref "U1") (pin "40") (pinfunction "21.4_40") (pintype "input"))
    )
    (net (code "107") (name "unconnected-(U1-21.5-Pad41)") (class "Default")
      (node (ref "U1") (pin "41") (pinfunction "21.5_41") (pintype "input"))
    )
    (net (code "108") (name "unconnected-(U1-21.6-Pad42)") (class "Default")
      (node (ref "U1") (pin "42") (pinfunction "21.6_42") (pintype "input"))
    )
    (net (code "109") (name "unconnected-(U1-21.7-Pad43)") (class "Default")
      (node (ref "U1") (pin "43") (pinfunction "21.7_43") (pintype "input"))
    )
    (net (code "110") (name "unconnected-(U1-22.0-Pad34)") (class "Default")
      (node (ref "U1") (pin "34") (pinfunction "22.0_34") (pintype "input"))
    )
    (net (code "111") (name "unconnected-(U1-22.1-Pad35)") (class "Default")
      (node (ref "U1") (pin "35") (pinfunction "22.1_35") (pintype "input"))
    )
    (net (code "112") (name "unconnected-(U1-23.1-Pad33)") (class "Default")
      (node (ref "U1") (pin "33") (pinfunction "23.1_33") (pintype "input"))
    )
    (net (code "113") (name "unconnected-(U1-33.6-Pad24)") (class "Default")
      (node (ref "U1") (pin "24") (pinfunction "33.6_24") (pintype "input"))
    )
    (net (code "114") (name "unconnected-(U1-33.8-Pad26)") (class "Default")
      (node (ref "U1") (pin "26") (pinfunction "33.8_26") (pintype "input"))
    )
    (net (code "115") (name "unconnected-(U1-33.11-Pad29)") (class "Default")
      (node (ref "U1") (pin "29") (pinfunction "33.11_29") (pintype "input"))
    )
    (net (code "116") (name "unconnected-(U1-A0-Pad21)") (class "Default")
      (node (ref "U1") (pin "21") (pinfunction "A0_21") (pintype "input"))
    )
    (net (code "117") (name "unconnected-(U1-A1-Pad20)") (class "Default")
      (node (ref "U1") (pin "20") (pinfunction "A1_20") (pintype "input"))
    )
    (net (code "118") (name "unconnected-(U1-A2-Pad19)") (class "Default")
      (node (ref "U1") (pin "19") (pinfunction "A2_19") (pintype "input"))
    )
    (net (code "119") (name "unconnected-(U1-A3-Pad18)") (class "Default")
      (node (ref "U1") (pin "18") (pinfunction "A3_18") (pintype "input"))
    )
    (net (code "120") (name "unconnected-(U1-A4-Pad17)") (class "Default")
      (node (ref "U1") (pin "17") (pinfunction "A4_17") (pintype "input"))
    )
    (net (code "121") (name "unconnected-(U1-A5-Pad16)") (class "Default")
      (node (ref "U1") (pin "16") (pinfunction "A5_16") (pintype "input"))
    )
    (net (code "122") (name "unconnected-(U1-A6-Pad15)") (class "Default")
      (node (ref "U1") (pin "15") (pinfunction "A6_15") (pintype "input"))
    )
    (net (code "123") (name "unconnected-(U1-A7-Pad14)") (class "Default")
      (node (ref "U1") (pin "14") (pinfunction "A7_14") (pintype "input"))
    )
    (net (code "124") (name "unconnected-(U1-A10-Pad12)") (class "Default")
      (node (ref "U1") (pin "12") (pinfunction "A10_12") (pintype "input"))
    )
    (net (code "125") (name "unconnected-(U1-A11-Pad11)") (class "Default")
      (node (ref "U1") (pin "11") (pinfunction "A11_11") (pintype "input"))
    )
    (net (code "126") (name "unconnected-(U1-A12-Pad10)") (class "Default")
      (node (ref "U1") (pin "10") (pinfunction "A12_10") (pintype "input"))
    )
    (net (code "127") (name "unconnected-(U1-A13-Pad9)") (class "Default")
      (node (ref "U1") (pin "9") (pinfunction "A13_9") (pintype "input"))
    )
    (net (code "128") (name "unconnected-(U1-A16-Pad8)") (class "Default")
      (node (ref "U1") (pin "8") (pinfunction "A16_8") (pintype "input"))
    )
    (net (code "129") (name "unconnected-(U1-A17-Pad7)") (class "Default")
      (node (ref "U1") (pin "7") (pinfunction "A17_7") (pintype "input"))
    )
    (net (code "130") (name "unconnected-(U1-A20-Pad6)") (class "Default")
      (node (ref "U1") (pin "6") (pinfunction "A20_6") (pintype "input"))
    )
    (net (code "131") (name "unconnected-(U1-A21-Pad5)") (class "Default")
      (node (ref "U1") (pin "5") (pinfunction "A21_5") (pintype "input"))
    )
    (net (code "132") (name "unconnected-(U1-A24-Pad122)") (class "Default")
      (node (ref "U1") (pin "122") (pinfunction "A24_122") (pintype "input"))
    )
    (net (code "133") (name "unconnected-(U1-A25-Pad121)") (class "Default")
      (node (ref "U1") (pin "121") (pinfunction "A25_121") (pintype "input"))
    )
    (net (code "134") (name "unconnected-(U1-A35-Pad120)") (class "Default")
      (node (ref "U1") (pin "120") (pinfunction "A35_120") (pintype "input"))
    )
    (net (code "135") (name "unconnected-(U1-A36-Pad119)") (class "Default")
      (node (ref "U1") (pin "119") (pinfunction "A36_119") (pintype "input"))
    )
    (net (code "136") (name "unconnected-(U1-A37-Pad118)") (class "Default")
      (node (ref "U1") (pin "118") (pinfunction "A37_118") (pintype "input"))
    )
    (net (code "137") (name "unconnected-(U1-A38-Pad117)") (class "Default")
      (node (ref "U1") (pin "117") (pinfunction "A38_117") (pintype "input"))
    )
    (net (code "138") (name "unconnected-(U1-A39-Pad116)") (class "Default")
      (node (ref "U1") (pin "116") (pinfunction "A39_116") (pintype "input"))
    )
    (net (code "139") (name "unconnected-(U1-A44-Pad115)") (class "Default")
      (node (ref "U1") (pin "115") (pinfunction "A44_115") (pintype "input"))
    )
    (net (code "140") (name "unconnected-(U1-A45-Pad114)") (class "Default")
      (node (ref "U1") (pin "114") (pinfunction "A45_114") (pintype "input"))
    )
    (net (code "141") (name "unconnected-(U1-A46-Pad113)") (class "Default")
      (node (ref "U1") (pin "113") (pinfunction "A46_113") (pintype "input"))
    )
    (net (code "142") (name "unconnected-(U1-A47-Pad112)") (class "Default")
      (node (ref "U1") (pin "112") (pinfunction "A47_112") (pintype "input"))
    )
    (net (code "143") (name "unconnected-(U1-A48-Pad111)") (class "Default")
      (node (ref "U1") (pin "111") (pinfunction "A48_111") (pintype "input"))
    )
    (net (code "144") (name "unconnected-(U1-A49-Pad110)") (class "Default")
      (node (ref "U1") (pin "110") (pinfunction "A49_110") (pintype "input"))
    )
    (net (code "145") (name "unconnected-(U1-ESR0-Pad48)") (class "Default")
      (node (ref "U1") (pin "48") (pinfunction "ESR0_48") (pintype "input"))
    )
    (net (code "146") (name "unconnected-(U1-ESR1-Pad47)") (class "Default")
      (node (ref "U1") (pin "47") (pinfunction "ESR1_47") (pintype "input"))
    )
    (net (code "147") (name "unconnected-(U31-Pad2)") (class "Default")
      (node (ref "U31") (pin "2") (pinfunction "2_2") (pintype "input"))
    )
    (net (code "148") (name "unconnected-(U31-Pad8)") (class "Default")
      (node (ref "U31") (pin "8") (pinfunction "8_8") (pintype "input"))
    )
    (net (code "149") (name "unconnected-(U35-Pad5)") (class "Default")
      (node (ref "U35") (pin "5") (pinfunction "5_5") (pintype "input"))
    )
    (net (code "150") (name "unconnected-(U35-Pad6)") (class "Default")
      (node (ref "U35") (pin "6") (pinfunction "6_6") (pintype "input"))
    )
    (net (code "151") (name "unconnected-(U36-Pad7)") (class "Default")
      (node (ref "U36") (pin "7") (pinfunction "7_7") (pintype "unspecified"))
    )
    (net (code "152") (name "unconnected-(U36-Pad8)") (class "Default")
      (node (ref "U36") (pin "8") (pinfunction "8_8") (pintype "unspecified"))
    )
  )
)
